# V1_0.net
KiCad netlist of a schematic drawn in Altium Designer
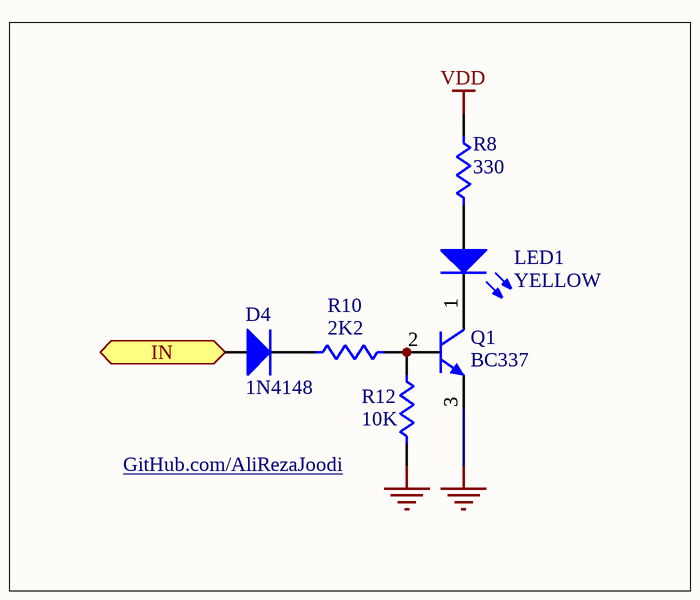
[diagram p0: V1.0.SchDoc]

(export (version "E")
  (design (tool "Eeschema 10.0.6"))
  (components
    (comp (ref "D4")
      (value "1N4148")
      (footprint "DIODE0.4_Glass")
      (description "Default Diode")
      (fields (field (name "MANUFACTURER") "Generic Components") (field (name "PUBLISHER") "Altium Limited"))
      (libsource (lib "Miscellaneous Devices") (part "Diode"))
    )
    (comp (ref "LED1")
      (value "YELLOW")
      (footprint "LED-5mm_Red")
      (description "Typical INFRARED GaAs LED")
      (fields (field (name "MANUFACTURER") "Generic Components") (field (name "PUBLISHER") "Altium Limited"))
      (libsource (lib "Miscellaneous Devices") (part "LED"))
    )
    (comp (ref "Q1")
      (value "BC337")
      (footprint "TO92C")
      (description "NPN Bipolar Transistor")
      (fields (field (name "MANUFACTURER") "Generic Components") (field (name "PUBLISHER") "Altium Limited"))
      (libsource (lib "Miscellaneous Devices") (part "NPN"))
    )
    (comp (ref "R8")
      (value "330")
      (footprint "AXIAL-0.4")
      (description "Resistor")
      (fields (field (name "MANUFACTURER") "Generic Components") (field (name "PUBLISHER") "Altium Limited"))
      (libsource (lib "Miscellaneous Devices") (part "Res1"))
    )
    (comp (ref "R10")
      (value "2K2")
      (footprint "AXIAL-0.4")
      (description "Resistor")
      (fields (field (name "MANUFACTURER") "Generic Components") (field (name "PUBLISHER") "Altium Limited"))
      (libsource (lib "Miscellaneous Devices") (part "Res1"))
    )
    (comp (ref "R12")
      (value "10K")
      (footprint "AXIAL-0.4")
      (description "Resistor")
      (fields (field (name "MANUFACTURER") "Generic Components") (field (name "PUBLISHER") "Altium Limited"))
      (libsource (lib "Miscellaneous Devices") (part "Res1"))
    )
  )
  (nets
    (net (code "1") (name "/IN") (class "Default")
      (node (ref "D4") (pin "1") (pinfunction "A_1") (pintype "passive"))
    )
    (net (code "2") (name "GND") (class "Default")
      (node (ref "Q1") (pin "3") (pinfunction "E_3") (pintype "passive"))
      (node (ref "R12") (pin "2") (pinfunction "2_2") (pintype "passive"))
    )
    (net (code "3") (name "Net-(D4-K)") (class "Default")
      (node (ref "D4") (pin "2") (pinfunction "K_2") (pintype "passive"))
      (node (ref "R10") (pin "2") (pinfunction "2_2") (pintype "passive"))
    )
    (net (code "4") (name "Net-(LED1-A)") (class "Default")
      (node (ref "LED1") (pin "1") (pinfunction "A_1") (pintype "passive"))
      (node (ref "R8") (pin "1") (pinfunction "1_1") (pintype "passive"))
    )
    (net (code "5") (name "Net-(LED1-K)") (class "Default")
      (node (ref "LED1") (pin "2") (pinfunction "K_2") (pintype "passive"))
      (node (ref "Q1") (pin "1") (pinfunction "C_1") (pintype "passive"))
    )
    (net (code "6") (name "Net-(Q1-B)") (class "Default")
      (node (ref "Q1") (pin "2") (pinfunction "B_2") (pintype "passive"))
      (node (ref "R10") (pin "1") (pinfunction "1_1") (pintype "passive"))
      (node (ref "R12") (pin "1") (pinfunction "1_1") (pintype "passive"))
    )
    (net (code "7") (name "VDD") (class "Default")
      (node (ref "R8") (pin "2") (pinfunction "2_2") (pintype "passive"))
    )
  )
)
